# oled.net
KiCad netlist of a schematic drawn in Altium Designer
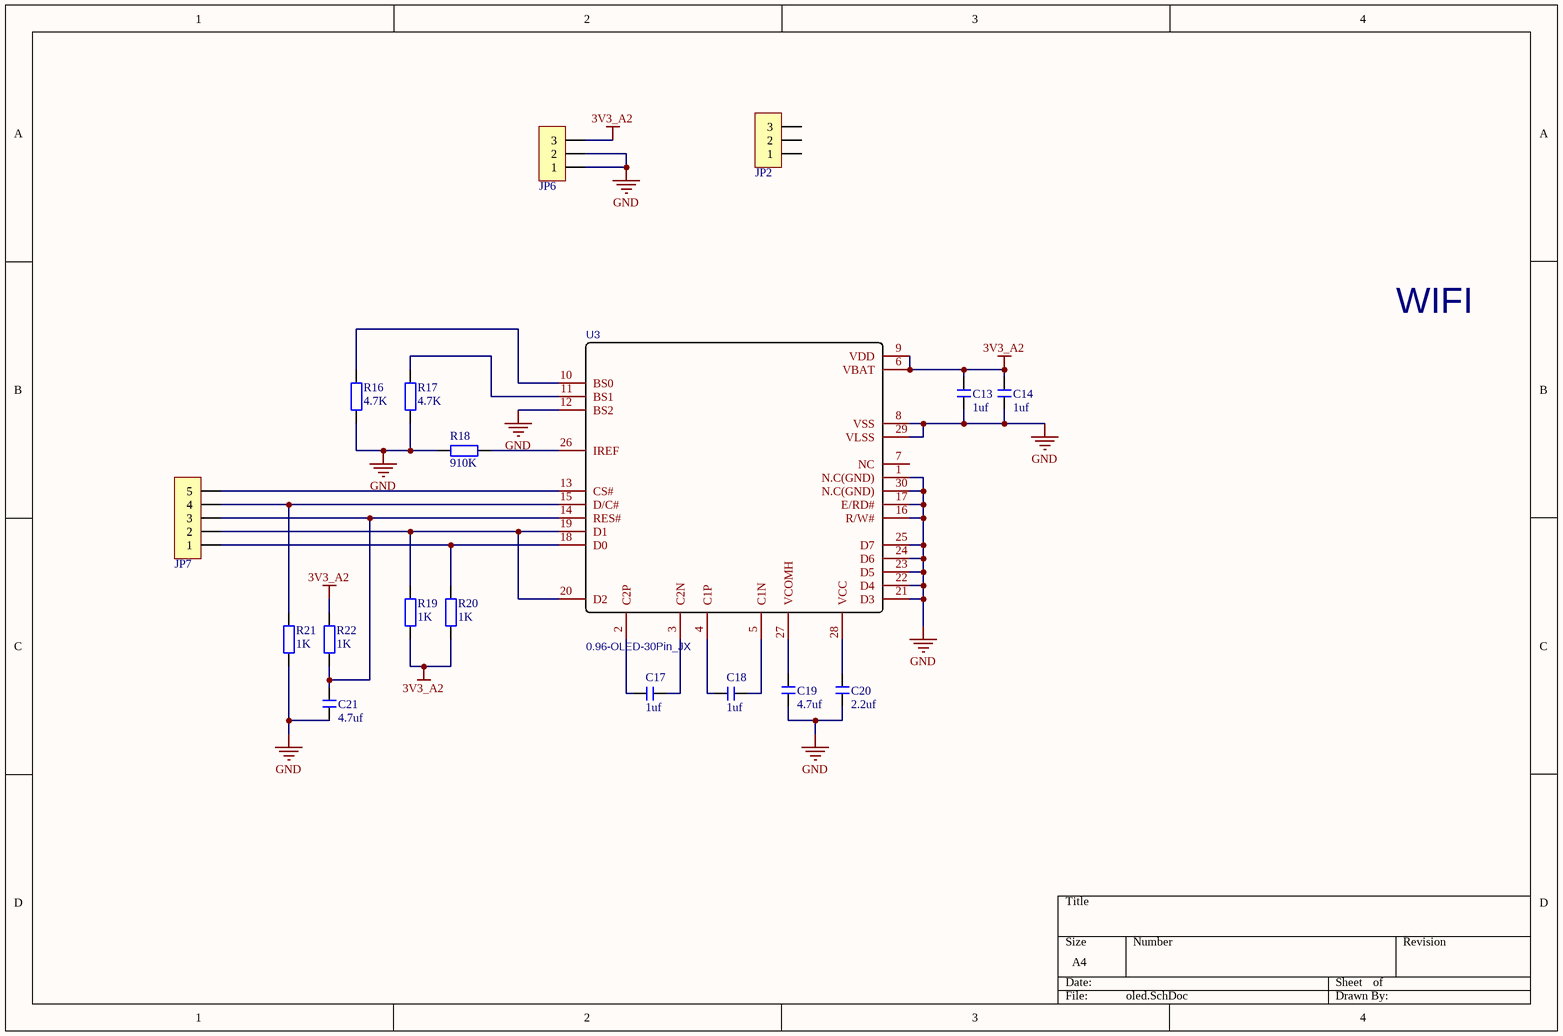
[diagram p0: oled.SchDoc]

(export (version "E")
  (design (tool "Eeschema 10.0.6"))
  (components
    (comp (ref "C13")
      (value "1uf")
      (footprint "C 0603")
      (description "无极性贴片电容")
      (fields (field (name "版权归属") "黎明电子style"))
      (libsource (lib "电阻-电容-电感") (part "C"))
    )
    (comp (ref "C14")
      (value "1uf")
      (footprint "C 0603")
      (description "无极性贴片电容")
      (fields (field (name "版权归属") "黎明电子style"))
      (libsource (lib "电阻-电容-电感") (part "C"))
    )
    (comp (ref "C17")
      (value "1uf")
      (footprint "C 0603")
      (description "无极性贴片电容")
      (fields (field (name "版权归属") "黎明电子style"))
      (libsource (lib "电阻-电容-电感") (part "C"))
    )
    (comp (ref "C18")
      (value "1uf")
      (footprint "C 0603")
      (description "无极性贴片电容")
      (fields (field (name "版权归属") "黎明电子style"))
      (libsource (lib "电阻-电容-电感") (part "C"))
    )
    (comp (ref "C19")
      (value "4.7uf")
      (footprint "C 0603")
      (description "无极性贴片电容")
      (fields (field (name "版权归属") "黎明电子style"))
      (libsource (lib "电阻-电容-电感") (part "C"))
    )
    (comp (ref "C20")
      (value "2.2uf")
      (footprint "C 0603")
      (description "无极性贴片电容")
      (fields (field (name "版权归属") "黎明电子style"))
      (libsource (lib "电阻-电容-电感") (part "C"))
    )
    (comp (ref "C21")
      (value "4.7uf")
      (footprint "C 0603")
      (description "无极性贴片电容")
      (fields (field (name "版权归属") "黎明电子style"))
      (libsource (lib "电阻-电容-电感") (part "C"))
    )
    (comp (ref "JP2")
      (value "HDR-1X3")
      (footprint "OLED_3PIN")
      (description "3P接插件")
      (fields (field (name "版权归属") "黎明电子style"))
      (libsource (lib "接插件") (part "Header 3"))
    )
    (comp (ref "JP6")
      (value "HDR-1X3")
      (footprint "OLED_3PIN")
      (description "3P接插件")
      (fields (field (name "版权归属") "黎明电子style"))
      (libsource (lib "接插件") (part "Header 3"))
    )
    (comp (ref "JP7")
      (value "HDR-1X5")
      (footprint "OLED_5PIN")
      (description "5P接插件")
      (fields (field (name "版权归属") "黎明电子style"))
      (libsource (lib "接插件") (part "Header 5"))
    )
    (comp (ref "R16")
      (value "4.7K")
      (footprint "R 0603")
      (description "贴片电阻")
      (fields (field (name "版权归属") "黎明电子style"))
      (libsource (lib "电阻-电容-电感") (part "R"))
    )
    (comp (ref "R17")
      (value "4.7K")
      (footprint "R 0603")
      (description "贴片电阻")
      (fields (field (name "版权归属") "黎明电子style"))
      (libsource (lib "电阻-电容-电感") (part "R"))
    )
    (comp (ref "R18")
      (value "910K")
      (footprint "R 0603")
      (description "贴片电阻")
      (fields (field (name "版权归属") "黎明电子style"))
      (libsource (lib "电阻-电容-电感") (part "R"))
    )
    (comp (ref "R19")
      (value "1K")
      (footprint "R 0603")
      (description "贴片电阻")
      (fields (field (name "版权归属") "黎明电子style"))
      (libsource (lib "电阻-电容-电感") (part "R"))
    )
    (comp (ref "R20")
      (value "1K")
      (footprint "R 0603")
      (description "贴片电阻")
      (fields (field (name "版权归属") "黎明电子style"))
      (libsource (lib "电阻-电容-电感") (part "R"))
    )
    (comp (ref "R21")
      (value "1K")
      (footprint "R 0603")
      (description "贴片电阻")
      (fields (field (name "版权归属") "黎明电子style"))
      (libsource (lib "电阻-电容-电感") (part "R"))
    )
    (comp (ref "R22")
      (value "1K")
      (footprint "R 0603")
      (description "贴片电阻")
      (fields (field (name "版权归属") "黎明电子style"))
      (libsource (lib "电阻-电容-电感") (part "R"))
    )
    (comp (ref "U3")
      (value "0.96-OLED-30Pin_JX")
      (footprint "SSD1306-30PIN_JX")
      (libsource (lib "Schlib1") (part "0.96-OLED-30Pin_JX"))
    )
  )
  (nets
    (net (code "1") (name "3V3_A2") (class "Default")
      (node (ref "C13") (pin "2") (pinfunction "2_2") (pintype "passive"))
      (node (ref "C14") (pin "2") (pinfunction "2_2") (pintype "passive"))
      (node (ref "JP6") (pin "3") (pinfunction "3_3") (pintype "passive"))
      (node (ref "R19") (pin "2") (pinfunction "2_2") (pintype "passive"))
      (node (ref "R20") (pin "2") (pinfunction "2_2") (pintype "passive"))
      (node (ref "R22") (pin "1") (pinfunction "1_1") (pintype "passive"))
      (node (ref "U3") (pin "6") (pinfunction "VBAT_6") (pintype "passive"))
      (node (ref "U3") (pin "9") (pinfunction "VDD_9") (pintype "passive"))
    )
    (net (code "2") (name "GND") (class "Default")
      (node (ref "C13") (pin "1") (pinfunction "1_1") (pintype "passive"))
      (node (ref "C14") (pin "1") (pinfunction "1_1") (pintype "passive"))
      (node (ref "C19") (pin "1") (pinfunction "1_1") (pintype "passive"))
      (node (ref "C20") (pin "1") (pinfunction "1_1") (pintype "passive"))
      (node (ref "C21") (pin "1") (pinfunction "1_1") (pintype "passive"))
      (node (ref "JP6") (pin "1") (pinfunction "1_1") (pintype "passive"))
      (node (ref "JP6") (pin "2") (pinfunction "2_2") (pintype "passive"))
      (node (ref "R16") (pin "2") (pinfunction "2_2") (pintype "passive"))
      (node (ref "R17") (pin "2") (pinfunction "2_2") (pintype "passive"))
      (node (ref "R18") (pin "1") (pinfunction "1_1") (pintype "passive"))
      (node (ref "R21") (pin "2") (pinfunction "2_2") (pintype "passive"))
      (node (ref "U3") (pin "1") (pinfunction "N.C(GND)_1") (pintype "passive"))
      (node (ref "U3") (pin "12") (pinfunction "BS2_12") (pintype "passive"))
      (node (ref "U3") (pin "16") (pinfunction "R/W#_16") (pintype "passive"))
      (node (ref "U3") (pin "17") (pinfunction "E/RD#_17") (pintype "passive"))
      (node (ref "U3") (pin "21") (pinfunction "D3_21") (pintype "passive"))
      (node (ref "U3") (pin "22") (pinfunction "D4_22") (pintype "passive"))
      (node (ref "U3") (pin "23") (pinfunction "D5_23") (pintype "passive"))
      (node (ref "U3") (pin "24") (pinfunction "D6_24") (pintype "passive"))
      (node (ref "U3") (pin "25") (pinfunction "D7_25") (pintype "passive"))
      (node (ref "U3") (pin "29") (pinfunction "VLSS_29") (pintype "passive"))
      (node (ref "U3") (pin "30") (pinfunction "N.C(GND)_30") (pintype "passive"))
      (node (ref "U3") (pin "8") (pinfunction "VSS_8") (pintype "passive"))
    )
    (net (code "3") (name "Net-(U3-BS0)") (class "Default")
      (node (ref "R16") (pin "1") (pinfunction "1_1") (pintype "passive"))
      (node (ref "U3") (pin "10") (pinfunction "BS0_10") (pintype "passive"))
    )
    (net (code "4") (name "Net-(U3-BS1)") (class "Default")
      (node (ref "R17") (pin "1") (pinfunction "1_1") (pintype "passive"))
      (node (ref "U3") (pin "11") (pinfunction "BS1_11") (pintype "passive"))
    )
    (net (code "5") (name "Net-(U3-C1N)") (class "Default")
      (node (ref "C18") (pin "1") (pinfunction "1_1") (pintype "passive"))
      (node (ref "U3") (pin "5") (pinfunction "C1N_5") (pintype "passive"))
    )
    (net (code "6") (name "Net-(U3-C1P)") (class "Default")
      (node (ref "C18") (pin "2") (pinfunction "2_2") (pintype "passive"))
      (node (ref "U3") (pin "4") (pinfunction "C1P_4") (pintype "passive"))
    )
    (net (code "7") (name "Net-(U3-C2N)") (class "Default")
      (node (ref "C17") (pin "1") (pinfunction "1_1") (pintype "passive"))
      (node (ref "U3") (pin "3") (pinfunction "C2N_3") (pintype "passive"))
    )
    (net (code "8") (name "Net-(U3-C2P)") (class "Default")
      (node (ref "C17") (pin "2") (pinfunction "2_2") (pintype "passive"))
      (node (ref "U3") (pin "2") (pinfunction "C2P_2") (pintype "passive"))
    )
    (net (code "9") (name "Net-(U3-CS#)") (class "Default")
      (node (ref "JP7") (pin "5") (pinfunction "5_5") (pintype "passive"))
      (node (ref "U3") (pin "13") (pinfunction "CS#_13") (pintype "passive"))
    )
    (net (code "10") (name "Net-(U3-D0)") (class "Default")
      (node (ref "JP7") (pin "1") (pinfunction "1_1") (pintype "passive"))
      (node (ref "R20") (pin "1") (pinfunction "1_1") (pintype "passive"))
      (node (ref "U3") (pin "18") (pinfunction "D0_18") (pintype "passive"))
    )
    (net (code "11") (name "Net-(U3-D1)") (class "Default")
      (node (ref "JP7") (pin "2") (pinfunction "2_2") (pintype "passive"))
      (node (ref "R19") (pin "1") (pinfunction "1_1") (pintype "passive"))
      (node (ref "U3") (pin "19") (pinfunction "D1_19") (pintype "passive"))
      (node (ref "U3") (pin "20") (pinfunction "D2_20") (pintype "passive"))
    )
    (net (code "12") (name "Net-(U3-D{slash}C#)") (class "Default")
      (node (ref "JP7") (pin "4") (pinfunction "4_4") (pintype "passive"))
      (node (ref "R21") (pin "1") (pinfunction "1_1") (pintype "passive"))
      (node (ref "U3") (pin "15") (pinfunction "D/C#_15") (pintype "passive"))
    )
    (net (code "13") (name "Net-(U3-IREF)") (class "Default")
      (node (ref "R18") (pin "2") (pinfunction "2_2") (pintype "passive"))
      (node (ref "U3") (pin "26") (pinfunction "IREF_26") (pintype "passive"))
    )
    (net (code "14") (name "Net-(U3-RES#)") (class "Default")
      (node (ref "C21") (pin "2") (pinfunction "2_2") (pintype "passive"))
      (node (ref "JP7") (pin "3") (pinfunction "3_3") (pintype "passive"))
      (node (ref "R22") (pin "2") (pinfunction "2_2") (pintype "passive"))
      (node (ref "U3") (pin "14") (pinfunction "RES#_14") (pintype "passive"))
    )
    (net (code "15") (name "Net-(U3-VCC)") (class "Default")
      (node (ref "C20") (pin "2") (pinfunction "2_2") (pintype "passive"))
      (node (ref "U3") (pin "28") (pinfunction "VCC_28") (pintype "passive"))
    )
    (net (code "16") (name "Net-(U3-VCOMH)") (class "Default")
      (node (ref "C19") (pin "2") (pinfunction "2_2") (pintype "passive"))
      (node (ref "U3") (pin "27") (pinfunction "VCOMH_27") (pintype "passive"))
    )
    (net (code "17") (name "unconnected-(JP2-Pad1)") (class "Default")
      (node (ref "JP2") (pin "1") (pinfunction "1_1") (pintype "passive"))
    )
    (net (code "18") (name "unconnected-(JP2-Pad2)") (class "Default")
      (node (ref "JP2") (pin "2") (pinfunction "2_2") (pintype "passive"))
    )
    (net (code "19") (name "unconnected-(JP2-Pad3)") (class "Default")
      (node (ref "JP2") (pin "3") (pinfunction "3_3") (pintype "passive"))
    )
    (net (code "20") (name "unconnected-(U3-NC-Pad7)") (class "Default")
      (node (ref "U3") (pin "7") (pinfunction "NC_7") (pintype "passive"))
    )
  )
)
